# ethernet_7.net
KiCad netlist of a schematic drawn in EAGLE
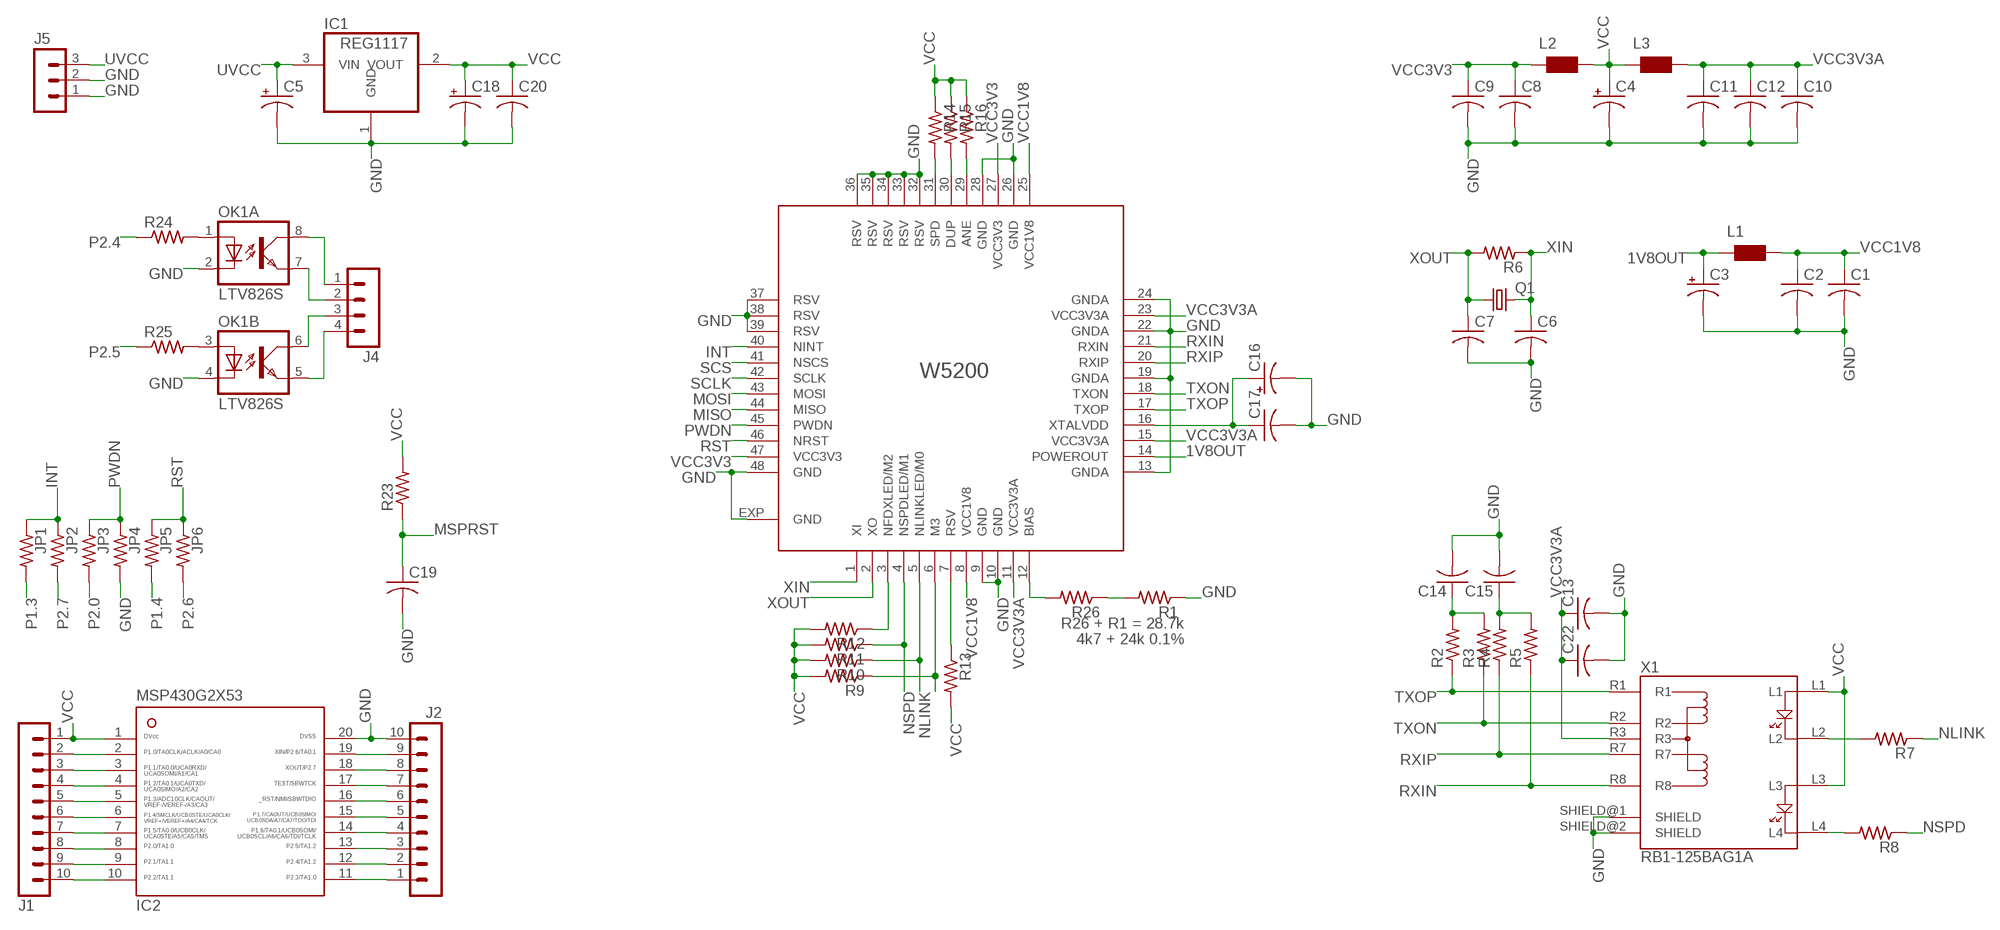
[diagram p0: schematic, sheet 1]

(export (version "E")
  (design (tool "Eeschema 10.0.6"))
  (components
    (comp (ref "C1")
      (value "C-USC0603")
      (footprint "eagle-import:C0603")
      (libsource (lib "eagle-import") (part "C-USC0603"))
    )
    (comp (ref "C2")
      (value "C-USC0603")
      (footprint "eagle-import:C0603")
      (libsource (lib "eagle-import") (part "C-USC0603"))
    )
    (comp (ref "C3")
      (value "CPOL-USA/3216-18R")
      (footprint "eagle-import:A_3216-18R")
      (libsource (lib "eagle-import") (part "CPOL-USA/3216-18R"))
    )
    (comp (ref "C4")
      (value "CPOL-USA/3216-18R")
      (footprint "eagle-import:A_3216-18R")
      (libsource (lib "eagle-import") (part "CPOL-USA/3216-18R"))
    )
    (comp (ref "C5")
      (value "CPOL-USB/3528-21R")
      (footprint "eagle-import:B_3528-21R")
      (libsource (lib "eagle-import") (part "CPOL-USB/3528-21R"))
    )
    (comp (ref "C6")
      (value "C-USC0603")
      (footprint "eagle-import:C0603")
      (libsource (lib "eagle-import") (part "C-USC0603"))
    )
    (comp (ref "C7")
      (value "C-USC0603")
      (footprint "eagle-import:C0603")
      (libsource (lib "eagle-import") (part "C-USC0603"))
    )
    (comp (ref "C8")
      (value "C-USC0603")
      (footprint "eagle-import:C0603")
      (libsource (lib "eagle-import") (part "C-USC0603"))
    )
    (comp (ref "C9")
      (value "C-USC0603")
      (footprint "eagle-import:C0603")
      (libsource (lib "eagle-import") (part "C-USC0603"))
    )
    (comp (ref "C10")
      (value "C-USC0603")
      (footprint "eagle-import:C0603")
      (libsource (lib "eagle-import") (part "C-USC0603"))
    )
    (comp (ref "C11")
      (value "C-USC0603")
      (footprint "eagle-import:C0603")
      (libsource (lib "eagle-import") (part "C-USC0603"))
    )
    (comp (ref "C12")
      (value "C-USC0603")
      (footprint "eagle-import:C0603")
      (libsource (lib "eagle-import") (part "C-USC0603"))
    )
    (comp (ref "C13")
      (value "C-USC0603")
      (footprint "eagle-import:C0603")
      (libsource (lib "eagle-import") (part "C-USC0603"))
    )
    (comp (ref "C14")
      (value "C-USC0603")
      (footprint "eagle-import:C0603")
      (libsource (lib "eagle-import") (part "C-USC0603"))
    )
    (comp (ref "C15")
      (value "C-USC0603")
      (footprint "eagle-import:C0603")
      (libsource (lib "eagle-import") (part "C-USC0603"))
    )
    (comp (ref "C16")
      (value "CPOL-USA/3216-18R")
      (footprint "eagle-import:A_3216-18R")
      (libsource (lib "eagle-import") (part "CPOL-USA/3216-18R"))
    )
    (comp (ref "C17")
      (value "C-USC0603")
      (footprint "eagle-import:C0603")
      (libsource (lib "eagle-import") (part "C-USC0603"))
    )
    (comp (ref "C18")
      (value "CPOL-USB/3528-21R")
      (footprint "eagle-import:B_3528-21R")
      (libsource (lib "eagle-import") (part "CPOL-USB/3528-21R"))
    )
    (comp (ref "C19")
      (value "C-USC0603")
      (footprint "eagle-import:C0603")
      (libsource (lib "eagle-import") (part "C-USC0603"))
    )
    (comp (ref "C20")
      (value "C-USC0603")
      (footprint "eagle-import:C0603")
      (libsource (lib "eagle-import") (part "C-USC0603"))
    )
    (comp (ref "C22")
      (value "C-USC0603")
      (footprint "eagle-import:C0603")
      (libsource (lib "eagle-import") (part "C-USC0603"))
    )
    (comp (ref "IC1")
      (value "REG1117")
      (footprint "eagle-import:SOT223")
      (libsource (lib "eagle-import") (part "REG1117"))
    )
    (comp (ref "IC2")
      (value "MSP430G2X53-20N20")
      (footprint "eagle-import:N20")
      (libsource (lib "eagle-import") (part "MSP430G2X53-20N20"))
    )
    (comp (ref "J1")
      (value "MA10-1NOTXT")
      (footprint "eagle-import:MA10-1-NOTXT")
      (libsource (lib "eagle-import") (part "MA10-1NOTXT"))
    )
    (comp (ref "J2")
      (value "MA10-1NOTXT")
      (footprint "eagle-import:MA10-1-NOTXT")
      (libsource (lib "eagle-import") (part "MA10-1NOTXT"))
    )
    (comp (ref "J4")
      (value "MA04-1-ALLV")
      (footprint "eagle-import:MA04-1")
      (libsource (lib "eagle-import") (part "MA04-1-ALLV"))
    )
    (comp (ref "J5")
      (value "MA03-1")
      (footprint "eagle-import:MA03-1")
      (libsource (lib "eagle-import") (part "MA03-1"))
    )
    (comp (ref "JP1")
      (value "R-US_R0603")
      (footprint "eagle-import:R0603")
      (libsource (lib "eagle-import") (part "R-US_R0603"))
    )
    (comp (ref "JP2")
      (value "R-US_R0603")
      (footprint "eagle-import:R0603")
      (libsource (lib "eagle-import") (part "R-US_R0603"))
    )
    (comp (ref "JP3")
      (value "R-US_R0603")
      (footprint "eagle-import:R0603")
      (libsource (lib "eagle-import") (part "R-US_R0603"))
    )
    (comp (ref "JP4")
      (value "R-US_R0603")
      (footprint "eagle-import:R0603")
      (libsource (lib "eagle-import") (part "R-US_R0603"))
    )
    (comp (ref "JP5")
      (value "R-US_R0603")
      (footprint "eagle-import:R0603")
      (libsource (lib "eagle-import") (part "R-US_R0603"))
    )
    (comp (ref "JP6")
      (value "R-US_R0603")
      (footprint "eagle-import:R0603")
      (libsource (lib "eagle-import") (part "R-US_R0603"))
    )
    (comp (ref "L1")
      (value "WE-CBF_0603")
      (footprint "eagle-import:0603")
      (libsource (lib "eagle-import") (part "WE-CBF_0603"))
    )
    (comp (ref "L2")
      (value "WE-CBF_0603")
      (footprint "eagle-import:0603")
      (libsource (lib "eagle-import") (part "WE-CBF_0603"))
    )
    (comp (ref "L3")
      (value "WE-CBF_0603")
      (footprint "eagle-import:0603")
      (libsource (lib "eagle-import") (part "WE-CBF_0603"))
    )
    (comp (ref "OK1")
      (value "LTV826S")
      (footprint "eagle-import:DIL8-SMD")
      (libsource (lib "eagle-import") (part "LTV826S"))
    )
    (comp (ref "Q1")
      (value "CRYSTALSM49")
      (footprint "eagle-import:SM49")
      (libsource (lib "eagle-import") (part "CRYSTALSM49"))
    )
    (comp (ref "R1")
      (value "R-US_R0603")
      (footprint "eagle-import:R0603")
      (libsource (lib "eagle-import") (part "R-US_R0603"))
    )
    (comp (ref "R2")
      (value "R-US_R0603")
      (footprint "eagle-import:R0603")
      (libsource (lib "eagle-import") (part "R-US_R0603"))
    )
    (comp (ref "R3")
      (value "R-US_R0603")
      (footprint "eagle-import:R0603")
      (libsource (lib "eagle-import") (part "R-US_R0603"))
    )
    (comp (ref "R4")
      (value "R-US_R0603")
      (footprint "eagle-import:R0603")
      (libsource (lib "eagle-import") (part "R-US_R0603"))
    )
    (comp (ref "R5")
      (value "R-US_R0603")
      (footprint "eagle-import:R0603")
      (libsource (lib "eagle-import") (part "R-US_R0603"))
    )
    (comp (ref "R6")
      (value "R-US_R0603")
      (footprint "eagle-import:R0603")
      (libsource (lib "eagle-import") (part "R-US_R0603"))
    )
    (comp (ref "R7")
      (value "R-US_R0603")
      (footprint "eagle-import:R0603")
      (libsource (lib "eagle-import") (part "R-US_R0603"))
    )
    (comp (ref "R8")
      (value "R-US_R0603")
      (footprint "eagle-import:R0603")
      (libsource (lib "eagle-import") (part "R-US_R0603"))
    )
    (comp (ref "R9")
      (value "R-US_R0603")
      (footprint "eagle-import:R0603")
      (libsource (lib "eagle-import") (part "R-US_R0603"))
    )
    (comp (ref "R10")
      (value "R-US_R0603")
      (footprint "eagle-import:R0603")
      (libsource (lib "eagle-import") (part "R-US_R0603"))
    )
    (comp (ref "R11")
      (value "R-US_R0603")
      (footprint "eagle-import:R0603")
      (libsource (lib "eagle-import") (part "R-US_R0603"))
    )
    (comp (ref "R12")
      (value "R-US_R0603")
      (footprint "eagle-import:R0603")
      (libsource (lib "eagle-import") (part "R-US_R0603"))
    )
    (comp (ref "R13")
      (value "R-US_R0603")
      (footprint "eagle-import:R0603")
      (libsource (lib "eagle-import") (part "R-US_R0603"))
    )
    (comp (ref "R14")
      (value "R-US_R0603")
      (footprint "eagle-import:R0603")
      (libsource (lib "eagle-import") (part "R-US_R0603"))
    )
    (comp (ref "R15")
      (value "R-US_R0603")
      (footprint "eagle-import:R0603")
      (libsource (lib "eagle-import") (part "R-US_R0603"))
    )
    (comp (ref "R16")
      (value "R-US_R0603")
      (footprint "eagle-import:R0603")
      (libsource (lib "eagle-import") (part "R-US_R0603"))
    )
    (comp (ref "R23")
      (value "R-US_R0603")
      (footprint "eagle-import:R0603")
      (libsource (lib "eagle-import") (part "R-US_R0603"))
    )
    (comp (ref "R24")
      (value "R-US_R0603")
      (footprint "eagle-import:R0603")
      (libsource (lib "eagle-import") (part "R-US_R0603"))
    )
    (comp (ref "R25")
      (value "R-US_R0603")
      (footprint "eagle-import:R0603")
      (libsource (lib "eagle-import") (part "R-US_R0603"))
    )
    (comp (ref "R26")
      (value "R-US_R0603")
      (footprint "eagle-import:R0603")
      (libsource (lib "eagle-import") (part "R-US_R0603"))
    )
    (comp (ref "W5200")
      (value "W52003")
      (footprint "eagle-import:QFN48-3")
      (libsource (lib "eagle-import") (part "W52003"))
    )
    (comp (ref "X1")
      (value "RB1-125BAG1A")
      (footprint "eagle-import:RB1-125BAG1A")
      (libsource (lib "eagle-import") (part "RB1-125BAG1A"))
    )
  )
  (nets
    (net (code "1") (name "/1V8OUT") (class "Default")
      (node (ref "C3") (pin "+") (pinfunction "+_+") (pintype "passive"))
      (node (ref "L1") (pin "1") (pinfunction "1_1") (pintype "passive"))
      (node (ref "W5200") (pin "14") (pinfunction "POWEROUT_14") (pintype "bidirectional"))
    )
    (net (code "2") (name "/GND") (class "Default")
      (node (ref "C1") (pin "2") (pinfunction "2_2") (pintype "passive"))
      (node (ref "C10") (pin "2") (pinfunction "2_2") (pintype "passive"))
      (node (ref "C11") (pin "2") (pinfunction "2_2") (pintype "passive"))
      (node (ref "C12") (pin "2") (pinfunction "2_2") (pintype "passive"))
      (node (ref "C13") (pin "2") (pinfunction "2_2") (pintype "passive"))
      (node (ref "C14") (pin "2") (pinfunction "2_2") (pintype "passive"))
      (node (ref "C15") (pin "2") (pinfunction "2_2") (pintype "passive"))
      (node (ref "C16") (pin "-") (pinfunction "-_-") (pintype "passive"))
      (node (ref "C17") (pin "2") (pinfunction "2_2") (pintype "passive"))
      (node (ref "C18") (pin "-") (pinfunction "-_-") (pintype "passive"))
      (node (ref "C19") (pin "2") (pinfunction "2_2") (pintype "passive"))
      (node (ref "C2") (pin "2") (pinfunction "2_2") (pintype "passive"))
      (node (ref "C20") (pin "2") (pinfunction "2_2") (pintype "passive"))
      (node (ref "C22") (pin "2") (pinfunction "2_2") (pintype "passive"))
      (node (ref "C3") (pin "-") (pinfunction "-_-") (pintype "passive"))
      (node (ref "C4") (pin "-") (pinfunction "-_-") (pintype "passive"))
      (node (ref "C5") (pin "-") (pinfunction "-_-") (pintype "passive"))
      (node (ref "C6") (pin "2") (pinfunction "2_2") (pintype "passive"))
      (node (ref "C7") (pin "2") (pinfunction "2_2") (pintype "passive"))
      (node (ref "C8") (pin "2") (pinfunction "2_2") (pintype "passive"))
      (node (ref "C9") (pin "2") (pinfunction "2_2") (pintype "passive"))
      (node (ref "IC1") (pin "1") (pinfunction "GND_1") (pintype "power_in"))
      (node (ref "IC2") (pin "20") (pinfunction "20_20") (pintype "bidirectional"))
      (node (ref "J2") (pin "10") (pinfunction "10_10") (pintype "passive"))
      (node (ref "J5") (pin "1") (pinfunction "1_1") (pintype "passive"))
      (node (ref "J5") (pin "2") (pinfunction "2_2") (pintype "passive"))
      (node (ref "JP4") (pin "2") (pinfunction "2_2") (pintype "passive"))
      (node (ref "OK1") (pin "2") (pinfunction "C_2") (pintype "passive"))
      (node (ref "OK1") (pin "4") (pinfunction "C_4") (pintype "passive"))
      (node (ref "R1") (pin "1") (pinfunction "1_1") (pintype "passive"))
      (node (ref "W5200") (pin "10") (pinfunction "GND_10") (pintype "bidirectional"))
      (node (ref "W5200") (pin "13") (pinfunction "GNDA_13") (pintype "bidirectional"))
      (node (ref "W5200") (pin "19") (pinfunction "GNDA_19") (pintype "bidirectional"))
      (node (ref "W5200") (pin "22") (pinfunction "GNDA_22") (pintype "bidirectional"))
      (node (ref "W5200") (pin "24") (pinfunction "GNDA_24") (pintype "bidirectional"))
      (node (ref "W5200") (pin "26") (pinfunction "GND_26") (pintype "bidirectional"))
      (node (ref "W5200") (pin "28") (pinfunction "GND_28") (pintype "bidirectional"))
      (node (ref "W5200") (pin "32") (pinfunction "RSV_32") (pintype "bidirectional"))
      (node (ref "W5200") (pin "33") (pinfunction "RSV_33") (pintype "bidirectional"))
      (node (ref "W5200") (pin "34") (pinfunction "RSV_34") (pintype "bidirectional"))
      (node (ref "W5200") (pin "35") (pinfunction "RSV_35") (pintype "bidirectional"))
      (node (ref "W5200") (pin "36") (pinfunction "RSV_36") (pintype "bidirectional"))
      (node (ref "W5200") (pin "37") (pinfunction "RSV_37") (pintype "bidirectional"))
      (node (ref "W5200") (pin "38") (pinfunction "RSV_38") (pintype "bidirectional"))
      (node (ref "W5200") (pin "39") (pinfunction "RSV_39") (pintype "bidirectional"))
      (node (ref "W5200") (pin "48") (pinfunction "GND_48") (pintype "bidirectional"))
      (node (ref "W5200") (pin "9") (pinfunction "GND_9") (pintype "bidirectional"))
      (node (ref "W5200") (pin "EXP") (pinfunction "GND_EXP") (pintype "bidirectional"))
      (node (ref "X1") (pin "SHIELD@1") (pinfunction "SHIELD_SHIELD@1") (pintype "bidirectional"))
      (node (ref "X1") (pin "SHIELD@2") (pinfunction "SHIELD_SHIELD@2") (pintype "bidirectional"))
    )
    (net (code "3") (name "/INT") (class "Default")
      (node (ref "JP1") (pin "1") (pinfunction "1_1") (pintype "passive"))
      (node (ref "JP2") (pin "1") (pinfunction "1_1") (pintype "passive"))
      (node (ref "W5200") (pin "40") (pinfunction "NINT_40") (pintype "bidirectional"))
    )
    (net (code "4") (name "/MISO") (class "Default")
      (node (ref "IC2") (pin "14") (pinfunction "14_14") (pintype "bidirectional"))
      (node (ref "J2") (pin "4") (pinfunction "4_4") (pintype "passive"))
      (node (ref "W5200") (pin "44") (pinfunction "MISO_44") (pintype "bidirectional"))
    )
    (net (code "5") (name "/MOSI") (class "Default")
      (node (ref "IC2") (pin "15") (pinfunction "15_15") (pintype "bidirectional"))
      (node (ref "J2") (pin "5") (pinfunction "5_5") (pintype "passive"))
      (node (ref "W5200") (pin "43") (pinfunction "MOSI_43") (pintype "bidirectional"))
    )
    (net (code "6") (name "/MSPRST") (class "Default")
      (node (ref "C19") (pin "1") (pinfunction "1_1") (pintype "passive"))
      (node (ref "IC2") (pin "16") (pinfunction "16_16") (pintype "bidirectional"))
      (node (ref "J2") (pin "6") (pinfunction "6_6") (pintype "passive"))
      (node (ref "R23") (pin "1") (pinfunction "1_1") (pintype "passive"))
    )
    (net (code "7") (name "/NLINK") (class "Default")
      (node (ref "R10") (pin "1") (pinfunction "1_1") (pintype "passive"))
      (node (ref "R7") (pin "1") (pinfunction "1_1") (pintype "passive"))
      (node (ref "W5200") (pin "5") (pinfunction "NLINKLED/M0_5") (pintype "bidirectional"))
    )
    (net (code "8") (name "/NSPD") (class "Default")
      (node (ref "R11") (pin "1") (pinfunction "1_1") (pintype "passive"))
      (node (ref "R8") (pin "1") (pinfunction "1_1") (pintype "passive"))
      (node (ref "W5200") (pin "4") (pinfunction "NSPDLED/M1_4") (pintype "bidirectional"))
    )
    (net (code "9") (name "/P1.3") (class "Default")
      (node (ref "IC2") (pin "5") (pinfunction "5_5") (pintype "bidirectional"))
      (node (ref "J1") (pin "5") (pinfunction "5_5") (pintype "passive"))
      (node (ref "JP1") (pin "2") (pinfunction "2_2") (pintype "passive"))
    )
    (net (code "10") (name "/P1.4") (class "Default")
      (node (ref "IC2") (pin "6") (pinfunction "6_6") (pintype "bidirectional"))
      (node (ref "J1") (pin "6") (pinfunction "6_6") (pintype "passive"))
      (node (ref "JP5") (pin "2") (pinfunction "2_2") (pintype "passive"))
    )
    (net (code "11") (name "/P2.0") (class "Default")
      (node (ref "IC2") (pin "8") (pinfunction "8_8") (pintype "bidirectional"))
      (node (ref "J1") (pin "8") (pinfunction "8_8") (pintype "passive"))
      (node (ref "JP3") (pin "2") (pinfunction "2_2") (pintype "passive"))
    )
    (net (code "12") (name "/P2.4") (class "Default")
      (node (ref "IC2") (pin "12") (pinfunction "12_12") (pintype "bidirectional"))
      (node (ref "J2") (pin "2") (pinfunction "2_2") (pintype "passive"))
      (node (ref "R24") (pin "1") (pinfunction "1_1") (pintype "passive"))
    )
    (net (code "13") (name "/P2.5") (class "Default")
      (node (ref "IC2") (pin "13") (pinfunction "13_13") (pintype "bidirectional"))
      (node (ref "J2") (pin "3") (pinfunction "3_3") (pintype "passive"))
      (node (ref "R25") (pin "1") (pinfunction "1_1") (pintype "passive"))
    )
    (net (code "14") (name "/P2.6") (class "Default")
      (node (ref "IC2") (pin "19") (pinfunction "19_19") (pintype "bidirectional"))
      (node (ref "J2") (pin "9") (pinfunction "9_9") (pintype "passive"))
      (node (ref "JP6") (pin "2") (pinfunction "2_2") (pintype "passive"))
    )
    (net (code "15") (name "/P2.7") (class "Default")
      (node (ref "IC2") (pin "18") (pinfunction "18_18") (pintype "bidirectional"))
      (node (ref "J2") (pin "8") (pinfunction "8_8") (pintype "passive"))
      (node (ref "JP2") (pin "2") (pinfunction "2_2") (pintype "passive"))
    )
    (net (code "16") (name "/PWDN") (class "Default")
      (node (ref "JP3") (pin "1") (pinfunction "1_1") (pintype "passive"))
      (node (ref "JP4") (pin "1") (pinfunction "1_1") (pintype "passive"))
      (node (ref "W5200") (pin "45") (pinfunction "PWDN_45") (pintype "bidirectional"))
    )
    (net (code "17") (name "/RST") (class "Default")
      (node (ref "JP5") (pin "1") (pinfunction "1_1") (pintype "passive"))
      (node (ref "JP6") (pin "1") (pinfunction "1_1") (pintype "passive"))
      (node (ref "W5200") (pin "46") (pinfunction "NRST_46") (pintype "bidirectional"))
    )
    (net (code "18") (name "/RXIN") (class "Default")
      (node (ref "R5") (pin "1") (pinfunction "1_1") (pintype "passive"))
      (node (ref "W5200") (pin "21") (pinfunction "RXIN_21") (pintype "bidirectional"))
      (node (ref "X1") (pin "R8") (pinfunction "R8_R8") (pintype "bidirectional"))
    )
    (net (code "19") (name "/RXIP") (class "Default")
      (node (ref "R4") (pin "1") (pinfunction "1_1") (pintype "passive"))
      (node (ref "W5200") (pin "20") (pinfunction "RXIP_20") (pintype "bidirectional"))
      (node (ref "X1") (pin "R7") (pinfunction "R7_R7") (pintype "bidirectional"))
    )
    (net (code "20") (name "/SCLK") (class "Default")
      (node (ref "IC2") (pin "7") (pinfunction "7_7") (pintype "bidirectional"))
      (node (ref "J1") (pin "7") (pinfunction "7_7") (pintype "passive"))
      (node (ref "W5200") (pin "42") (pinfunction "SCLK_42") (pintype "bidirectional"))
    )
    (net (code "21") (name "/SCS") (class "Default")
      (node (ref "IC2") (pin "2") (pinfunction "2_2") (pintype "bidirectional"))
      (node (ref "J1") (pin "2") (pinfunction "2_2") (pintype "passive"))
      (node (ref "W5200") (pin "41") (pinfunction "NSCS_41") (pintype "bidirectional"))
    )
    (net (code "22") (name "/TXON") (class "Default")
      (node (ref "R3") (pin "1") (pinfunction "1_1") (pintype "passive"))
      (node (ref "W5200") (pin "18") (pinfunction "TXON_18") (pintype "bidirectional"))
      (node (ref "X1") (pin "R2") (pinfunction "R2_R2") (pintype "bidirectional"))
    )
    (net (code "23") (name "/TXOP") (class "Default")
      (node (ref "R2") (pin "1") (pinfunction "1_1") (pintype "passive"))
      (node (ref "W5200") (pin "17") (pinfunction "TXOP_17") (pintype "bidirectional"))
      (node (ref "X1") (pin "R1") (pinfunction "R1_R1") (pintype "bidirectional"))
    )
    (net (code "24") (name "/UVCC") (class "Default")
      (node (ref "C5") (pin "+") (pinfunction "+_+") (pintype "passive"))
      (node (ref "IC1") (pin "3") (pinfunction "VIN_3") (pintype "input"))
      (node (ref "J5") (pin "3") (pinfunction "3_3") (pintype "passive"))
    )
    (net (code "25") (name "/VCC") (class "Default")
      (node (ref "C18") (pin "+") (pinfunction "+_+") (pintype "passive"))
      (node (ref "C20") (pin "1") (pinfunction "1_1") (pintype "passive"))
      (node (ref "C4") (pin "+") (pinfunction "+_+") (pintype "passive"))
      (node (ref "IC1") (pin "2") (pinfunction "VOUT_2") (pintype "output"))
      (node (ref "IC2") (pin "1") (pinfunction "1_1") (pintype "bidirectional"))
      (node (ref "J1") (pin "1") (pinfunction "1_1") (pintype "passive"))
      (node (ref "L2") (pin "2") (pinfunction "2_2") (pintype "passive"))
      (node (ref "L3") (pin "1") (pinfunction "1_1") (pintype "passive"))
      (node (ref "R10") (pin "2") (pinfunction "2_2") (pintype "passive"))
      (node (ref "R11") (pin "2") (pinfunction "2_2") (pintype "passive"))
      (node (ref "R12") (pin "2") (pinfunction "2_2") (pintype "passive"))
      (node (ref "R13") (pin "2") (pinfunction "2_2") (pintype "passive"))
      (node (ref "R14") (pin "1") (pinfunction "1_1") (pintype "passive"))
      (node (ref "R15") (pin "1") (pinfunction "1_1") (pintype "passive"))
      (node (ref "R16") (pin "1") (pinfunction "1_1") (pintype "passive"))
      (node (ref "R23") (pin "2") (pinfunction "2_2") (pintype "passive"))
      (node (ref "R9") (pin "2") (pinfunction "2_2") (pintype "passive"))
      (node (ref "X1") (pin "L1") (pinfunction "L1_L1") (pintype "bidirectional"))
      (node (ref "X1") (pin "L3") (pinfunction "L3_L3") (pintype "bidirectional"))
    )
    (net (code "26") (name "/VCC1V8") (class "Default")
      (node (ref "C1") (pin "1") (pinfunction "1_1") (pintype "passive"))
      (node (ref "C2") (pin "1") (pinfunction "1_1") (pintype "passive"))
      (node (ref "L1") (pin "2") (pinfunction "2_2") (pintype "passive"))
      (node (ref "W5200") (pin "25") (pinfunction "VCC1V8_25") (pintype "bidirectional"))
      (node (ref "W5200") (pin "8") (pinfunction "VCC1V8_8") (pintype "bidirectional"))
    )
    (net (code "27") (name "/VCC3V3") (class "Default")
      (node (ref "C8") (pin "1") (pinfunction "1_1") (pintype "passive"))
      (node (ref "C9") (pin "1") (pinfunction "1_1") (pintype "passive"))
      (node (ref "L2") (pin "1") (pinfunction "1_1") (pintype "passive"))
      (node (ref "W5200") (pin "27") (pinfunction "VCC3V3_27") (pintype "bidirectional"))
      (node (ref "W5200") (pin "47") (pinfunction "VCC3V3_47") (pintype "bidirectional"))
    )
    (net (code "28") (name "/VCC3V3A") (class "Default")
      (node (ref "C10") (pin "1") (pinfunction "1_1") (pintype "passive"))
      (node (ref "C11") (pin "1") (pinfunction "1_1") (pintype "passive"))
      (node (ref "C12") (pin "1") (pinfunction "1_1") (pintype "passive"))
      (node (ref "C13") (pin "1") (pinfunction "1_1") (pintype "passive"))
      (node (ref "C22") (pin "1") (pinfunction "1_1") (pintype "passive"))
      (node (ref "L3") (pin "2") (pinfunction "2_2") (pintype "passive"))
      (node (ref "W5200") (pin "11") (pinfunction "VCC3V3A_11") (pintype "bidirectional"))
      (node (ref "W5200") (pin "15") (pinfunction "VCC3V3A_15") (pintype "bidirectional"))
      (node (ref "W5200") (pin "23") (pinfunction "VCC3V3A_23") (pintype "bidirectional"))
      (node (ref "X1") (pin "R3") (pinfunction "R3_R3") (pintype "bidirectional"))
    )
    (net (code "29") (name "/XIN") (class "Default")
      (node (ref "C6") (pin "1") (pinfunction "1_1") (pintype "passive"))
      (node (ref "Q1") (pin "2") (pinfunction "2_2") (pintype "passive"))
      (node (ref "R6") (pin "1") (pinfunction "1_1") (pintype "passive"))
      (node (ref "W5200") (pin "1") (pinfunction "XI_1") (pintype "bidirectional"))
    )
    (net (code "30") (name "/XOUT") (class "Default")
      (node (ref "C7") (pin "1") (pinfunction "1_1") (pintype "passive"))
      (node (ref "Q1") (pin "1") (pinfunction "1_1") (pintype "passive"))
      (node (ref "R6") (pin "2") (pinfunction "2_2") (pintype "passive"))
      (node (ref "W5200") (pin "2") (pinfunction "XO_2") (pintype "bidirectional"))
    )
    (net (code "31") (name "Net-(C14-Pad1)") (class "Default")
      (node (ref "C14") (pin "1") (pinfunction "1_1") (pintype "passive"))
      (node (ref "R2") (pin "2") (pinfunction "2_2") (pintype "passive"))
      (node (ref "R3") (pin "2") (pinfunction "2_2") (pintype "passive"))
    )
    (net (code "32") (name "Net-(C15-Pad1)") (class "Default")
      (node (ref "C15") (pin "1") (pinfunction "1_1") (pintype "passive"))
      (node (ref "R4") (pin "2") (pinfunction "2_2") (pintype "passive"))
      (node (ref "R5") (pin "2") (pinfunction "2_2") (pintype "passive"))
    )
    (net (code "33") (name "Net-(IC2-Pad3)") (class "Default")
      (node (ref "IC2") (pin "3") (pinfunction "3_3") (pintype "bidirectional"))
      (node (ref "J1") (pin "3") (pinfunction "3_3") (pintype "passive"))
    )
    (net (code "34") (name "Net-(IC2-Pad4)") (class "Default")
      (node (ref "IC2") (pin "4") (pinfunction "4_4") (pintype "bidirectional"))
      (node (ref "J1") (pin "4") (pinfunction "4_4") (pintype "passive"))
    )
    (net (code "35") (name "Net-(IC2-Pad9)") (class "Default")
      (node (ref "IC2") (pin "9") (pinfunction "9_9") (pintype "bidirectional"))
      (node (ref "J1") (pin "9") (pinfunction "9_9") (pintype "passive"))
    )
    (net (code "36") (name "Net-(IC2-Pad10)") (class "Default")
      (node (ref "IC2") (pin "10") (pinfunction "10_10") (pintype "bidirectional"))
      (node (ref "J1") (pin "10") (pinfunction "10_10") (pintype "passive"))
    )
    (net (code "37") (name "Net-(IC2-Pad11)") (class "Default")
      (node (ref "IC2") (pin "11") (pinfunction "11_11") (pintype "bidirectional"))
      (node (ref "J2") (pin "1") (pinfunction "1_1") (pintype "passive"))
    )
    (net (code "38") (name "Net-(IC2-Pad17)") (class "Default")
      (node (ref "IC2") (pin "17") (pinfunction "17_17") (pintype "bidirectional"))
      (node (ref "J2") (pin "7") (pinfunction "7_7") (pintype "passive"))
    )
    (net (code "39") (name "Net-(OK1A-A)") (class "Default")
      (node (ref "OK1") (pin "1") (pinfunction "A_1") (pintype "passive"))
      (node (ref "R24") (pin "2") (pinfunction "2_2") (pintype "passive"))
    )
    (net (code "40") (name "Net-(OK1A-COL)") (class "Default")
      (node (ref "J4") (pin "1") (pinfunction "1_1") (pintype "passive"))
      (node (ref "OK1") (pin "8") (pinfunction "COL_8") (pintype "passive"))
    )
    (net (code "41") (name "Net-(OK1A-EMIT)") (class "Default")
      (node (ref "J4") (pin "2") (pinfunction "2_2") (pintype "passive"))
      (node (ref "OK1") (pin "7") (pinfunction "EMIT_7") (pintype "passive"))
    )
    (net (code "42") (name "Net-(OK1B-A)") (class "Default")
      (node (ref "OK1") (pin "3") (pinfunction "A_3") (pintype "passive"))
      (node (ref "R25") (pin "2") (pinfunction "2_2") (pintype "passive"))
    )
    (net (code "43") (name "Net-(OK1B-COL)") (class "Default")
      (node (ref "J4") (pin "3") (pinfunction "3_3") (pintype "passive"))
      (node (ref "OK1") (pin "6") (pinfunction "COL_6") (pintype "passive"))
    )
    (net (code "44") (name "Net-(OK1B-EMIT)") (class "Default")
      (node (ref "J4") (pin "4") (pinfunction "4_4") (pintype "passive"))
      (node (ref "OK1") (pin "5") (pinfunction "EMIT_5") (pintype "passive"))
    )
    (net (code "45") (name "Net-(R1-Pad2)") (class "Default")
      (node (ref "R1") (pin "2") (pinfunction "2_2") (pintype "passive"))
      (node (ref "R26") (pin "1") (pinfunction "1_1") (pintype "passive"))
    )
    (net (code "46") (name "Net-(R7-Pad2)") (class "Default")
      (node (ref "R7") (pin "2") (pinfunction "2_2") (pintype "passive"))
      (node (ref "X1") (pin "L2") (pinfunction "L2_L2") (pintype "bidirectional"))
    )
    (net (code "47") (name "Net-(R8-Pad2)") (class "Default")
      (node (ref "R8") (pin "2") (pinfunction "2_2") (pintype "passive"))
      (node (ref "X1") (pin "L4") (pinfunction "L4_L4") (pintype "bidirectional"))
    )
    (net (code "48") (name "Net-(R13-Pad1)") (class "Default")
      (node (ref "R13") (pin "1") (pinfunction "1_1") (pintype "passive"))
      (node (ref "W5200") (pin "7") (pinfunction "RSV_7") (pintype "bidirectional"))
    )
    (net (code "49") (name "Net-(W5200-ANE)") (class "Default")
      (node (ref "R16") (pin "2") (pinfunction "2_2") (pintype "passive"))
      (node (ref "W5200") (pin "29") (pinfunction "ANE_29") (pintype "bidirectional"))
    )
    (net (code "50") (name "Net-(W5200-BIAS)") (class "Default")
      (node (ref "R26") (pin "2") (pinfunction "2_2") (pintype "passive"))
      (node (ref "W5200") (pin "12") (pinfunction "BIAS_12") (pintype "bidirectional"))
    )
    (net (code "51") (name "Net-(W5200-DUP)") (class "Default")
      (node (ref "R15") (pin "2") (pinfunction "2_2") (pintype "passive"))
      (node (ref "W5200") (pin "30") (pinfunction "DUP_30") (pintype "bidirectional"))
    )
    (net (code "52") (name "Net-(W5200-M3)") (class "Default")
      (node (ref "R9") (pin "1") (pinfunction "1_1") (pintype "passive"))
      (node (ref "W5200") (pin "6") (pinfunction "M3_6") (pintype "bidirectional"))
    )
    (net (code "53") (name "Net-(W5200-NFDXLED{slash}M2)") (class "Default")
      (node (ref "R12") (pin "1") (pinfunction "1_1") (pintype "passive"))
      (node (ref "W5200") (pin "3") (pinfunction "NFDXLED/M2_3") (pintype "bidirectional"))
    )
    (net (code "54") (name "Net-(W5200-SPD)") (class "Default")
      (node (ref "R14") (pin "2") (pinfunction "2_2") (pintype "passive"))
      (node (ref "W5200") (pin "31") (pinfunction "SPD_31") (pintype "bidirectional"))
    )
    (net (code "55") (name "Net-(W5200-XTALVDD)") (class "Default")
      (node (ref "C16") (pin "+") (pinfunction "+_+") (pintype "passive"))
      (node (ref "C17") (pin "1") (pinfunction "1_1") (pintype "passive"))
      (node (ref "W5200") (pin "16") (pinfunction "XTALVDD_16") (pintype "bidirectional"))
    )
  )
)
